# pic_dip_breakout.net
KiCad netlist of a schematic drawn in EAGLE
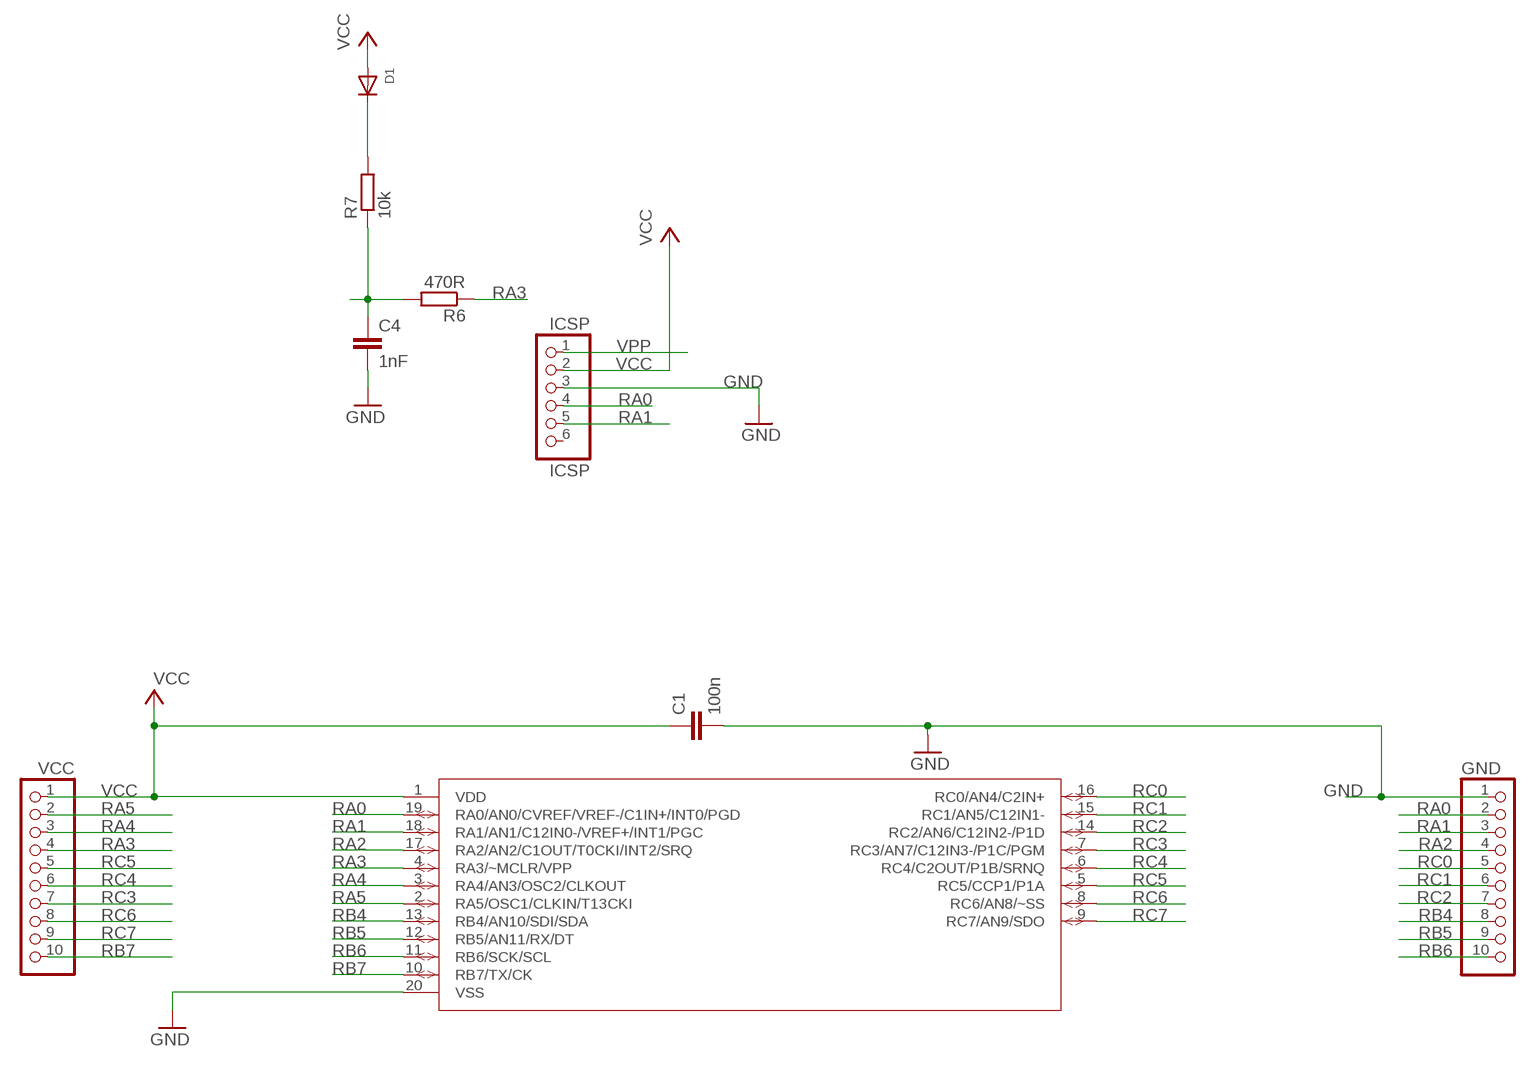
[diagram p0: schematic, sheet 1]

(export (version "E")
  (design (tool "Eeschema 10.0.6"))
  (components
    (comp (ref "C1")
      (value "100n")
      (footprint "eagle-import:C0805")
      (libsource (lib "eagle-import") (part "C-EUC0805"))
    )
    (comp (ref "C4")
      (value "1nF")
      (footprint "eagle-import:C0805")
      (libsource (lib "eagle-import") (part "resistor_C-EUC0805"))
    )
    (comp (ref "D1")
      (value "DIODESOD-323F")
      (footprint "eagle-import:SOD-323F")
      (libsource (lib "eagle-import") (part "DIODESOD-323F"))
    )
    (comp (ref "GND")
      (value "PH1X10OCT076")
      (footprint "eagle-import:PH1X10OCT76")
      (libsource (lib "eagle-import") (part "PH1X10OCT076"))
    )
    (comp (ref "ICSP")
      (value "ICSP")
      (footprint "eagle-import:1X06")
      (libsource (lib "eagle-import") (part "PINHD-1X6"))
    )
    (comp (ref "R6")
      (value "470R")
      (footprint "eagle-import:R0805")
      (libsource (lib "eagle-import") (part "R-EU_R0805"))
    )
    (comp (ref "R7")
      (value "10k")
      (footprint "eagle-import:R0805")
      (libsource (lib "eagle-import") (part "R-EU_R0805"))
    )
    (comp (ref "U$1")
      (value "PIC18F14K22-I/P")
      (footprint "eagle-import:DIP254P762X533-20")
      (fields (field (name "MPN") "PIC18F14k22-I/P"))
      (libsource (lib "eagle-import") (part "PIC18F14K22-I/P"))
    )
    (comp (ref "VCC")
      (value "PH1X10OCT076")
      (footprint "eagle-import:PH1X10OCT76")
      (libsource (lib "eagle-import") (part "PH1X10OCT076"))
    )
  )
  (nets
    (net (code "1") (name "/RA0") (class "Default")
      (node (ref "GND") (pin "2") (pinfunction "2_2") (pintype "passive"))
      (node (ref "ICSP") (pin "4") (pinfunction "4_4") (pintype "passive"))
      (node (ref "U$1") (pin "19") (pinfunction "RA0/AN0/CVREF/VREF-/C1IN+/INT0/PGD_19") (pintype "bidirectional"))
    )
    (net (code "2") (name "/RA1") (class "Default")
      (node (ref "GND") (pin "3") (pinfunction "3_3") (pintype "passive"))
      (node (ref "ICSP") (pin "5") (pinfunction "5_5") (pintype "passive"))
      (node (ref "U$1") (pin "18") (pinfunction "RA1/AN1/C12IN0-/VREF+/INT1/PGC_18") (pintype "bidirectional"))
    )
    (net (code "3") (name "/RA2") (class "Default")
      (node (ref "GND") (pin "4") (pinfunction "4_4") (pintype "passive"))
      (node (ref "U$1") (pin "17") (pinfunction "RA2/AN2/C1OUT/T0CKI/INT2/SRQ_17") (pintype "bidirectional"))
    )
    (net (code "4") (name "/RA3") (class "Default")
      (node (ref "R6") (pin "1") (pinfunction "1_1") (pintype "passive"))
      (node (ref "U$1") (pin "4") (pinfunction "RA3/~{MCLR/VPP}_4") (pintype "bidirectional"))
      (node (ref "VCC") (pin "4") (pinfunction "4_4") (pintype "passive"))
    )
    (net (code "5") (name "/RA4") (class "Default")
      (node (ref "U$1") (pin "3") (pinfunction "RA4/AN3/OSC2/CLKOUT_3") (pintype "bidirectional"))
      (node (ref "VCC") (pin "3") (pinfunction "3_3") (pintype "passive"))
    )
    (net (code "6") (name "/RA5") (class "Default")
      (node (ref "U$1") (pin "2") (pinfunction "RA5/OSC1/CLKIN/T13CKI_2") (pintype "bidirectional"))
      (node (ref "VCC") (pin "2") (pinfunction "2_2") (pintype "passive"))
    )
    (net (code "7") (name "/RB4") (class "Default")
      (node (ref "GND") (pin "8") (pinfunction "8_8") (pintype "passive"))
      (node (ref "U$1") (pin "13") (pinfunction "RB4/AN10/SDI/SDA_13") (pintype "bidirectional"))
    )
    (net (code "8") (name "/RB5") (class "Default")
      (node (ref "GND") (pin "9") (pinfunction "9_9") (pintype "passive"))
      (node (ref "U$1") (pin "12") (pinfunction "RB5/AN11/RX/DT_12") (pintype "bidirectional"))
    )
    (net (code "9") (name "/RB6") (class "Default")
      (node (ref "GND") (pin "10") (pinfunction "10_10") (pintype "passive"))
      (node (ref "U$1") (pin "11") (pinfunction "RB6/SCK/SCL_11") (pintype "bidirectional"))
    )
    (net (code "10") (name "/RB7") (class "Default")
      (node (ref "U$1") (pin "10") (pinfunction "RB7/TX/CK_10") (pintype "bidirectional"))
      (node (ref "VCC") (pin "10") (pinfunction "10_10") (pintype "passive"))
    )
    (net (code "11") (name "/RC0") (class "Default")
      (node (ref "GND") (pin "5") (pinfunction "5_5") (pintype "passive"))
      (node (ref "U$1") (pin "16") (pinfunction "RC0/AN4/C2IN+_16") (pintype "bidirectional"))
    )
    (net (code "12") (name "/RC1") (class "Default")
      (node (ref "GND") (pin "6") (pinfunction "6_6") (pintype "passive"))
      (node (ref "U$1") (pin "15") (pinfunction "RC1/AN5/C12IN1-_15") (pintype "bidirectional"))
    )
    (net (code "13") (name "/RC2") (class "Default")
      (node (ref "GND") (pin "7") (pinfunction "7_7") (pintype "passive"))
      (node (ref "U$1") (pin "14") (pinfunction "RC2/AN6/C12IN2-/P1D_14") (pintype "bidirectional"))
    )
    (net (code "14") (name "/RC3") (class "Default")
      (node (ref "U$1") (pin "7") (pinfunction "RC3/AN7/C12IN3-/P1C/PGM_7") (pintype "bidirectional"))
      (node (ref "VCC") (pin "7") (pinfunction "7_7") (pintype "passive"))
    )
    (net (code "15") (name "/RC4") (class "Default")
      (node (ref "U$1") (pin "6") (pinfunction "RC4/C2OUT/P1B/SRNQ_6") (pintype "bidirectional"))
      (node (ref "VCC") (pin "6") (pinfunction "6_6") (pintype "passive"))
    )
    (net (code "16") (name "/RC5") (class "Default")
      (node (ref "U$1") (pin "5") (pinfunction "RC5/CCP1/P1A_5") (pintype "bidirectional"))
      (node (ref "VCC") (pin "5") (pinfunction "5_5") (pintype "passive"))
    )
    (net (code "17") (name "/RC6") (class "Default")
      (node (ref "U$1") (pin "8") (pinfunction "RC6/AN8/~{SS}_8") (pintype "bidirectional"))
      (node (ref "VCC") (pin "8") (pinfunction "8_8") (pintype "passive"))
    )
    (net (code "18") (name "/RC7") (class "Default")
      (node (ref "U$1") (pin "9") (pinfunction "RC7/AN9/SDO_9") (pintype "bidirectional"))
      (node (ref "VCC") (pin "9") (pinfunction "9_9") (pintype "passive"))
    )
    (net (code "19") (name "/VPP") (class "Default")
      (node (ref "C4") (pin "1") (pinfunction "1_1") (pintype "passive"))
      (node (ref "ICSP") (pin "1") (pinfunction "1_1") (pintype "passive"))
      (node (ref "R6") (pin "2") (pinfunction "2_2") (pintype "passive"))
      (node (ref "R7") (pin "1") (pinfunction "1_1") (pintype "passive"))
    )
    (net (code "20") (name "GND") (class "Default")
      (node (ref "C1") (pin "2") (pinfunction "2_2") (pintype "passive"))
      (node (ref "C4") (pin "2") (pinfunction "2_2") (pintype "passive"))
      (node (ref "GND") (pin "1") (pinfunction "1_1") (pintype "passive"))
      (node (ref "ICSP") (pin "3") (pinfunction "3_3") (pintype "passive"))
      (node (ref "U$1") (pin "20") (pinfunction "VSS_20") (pintype "power_in"))
    )
    (net (code "21") (name "Net-(D1-PadC)") (class "Default")
      (node (ref "D1") (pin "C") (pinfunction "C_C") (pintype "passive"))
      (node (ref "R7") (pin "2") (pinfunction "2_2") (pintype "passive"))
    )
    (net (code "22") (name "VCC") (class "Default")
      (node (ref "C1") (pin "1") (pinfunction "1_1") (pintype "passive"))
      (node (ref "D1") (pin "A") (pinfunction "A_A") (pintype "passive"))
      (node (ref "ICSP") (pin "2") (pinfunction "2_2") (pintype "passive"))
      (node (ref "U$1") (pin "1") (pinfunction "VDD_1") (pintype "power_in"))
      (node (ref "VCC") (pin "1") (pinfunction "1_1") (pintype "passive"))
    )
    (net (code "23") (name "unconnected-(ICSP-Pad6)") (class "Default")
      (node (ref "ICSP") (pin "6") (pinfunction "6_6") (pintype "passive"))
    )
  )
)
